# 2_Main_V2_4.net
KiCad netlist of a schematic drawn in Altium Designer
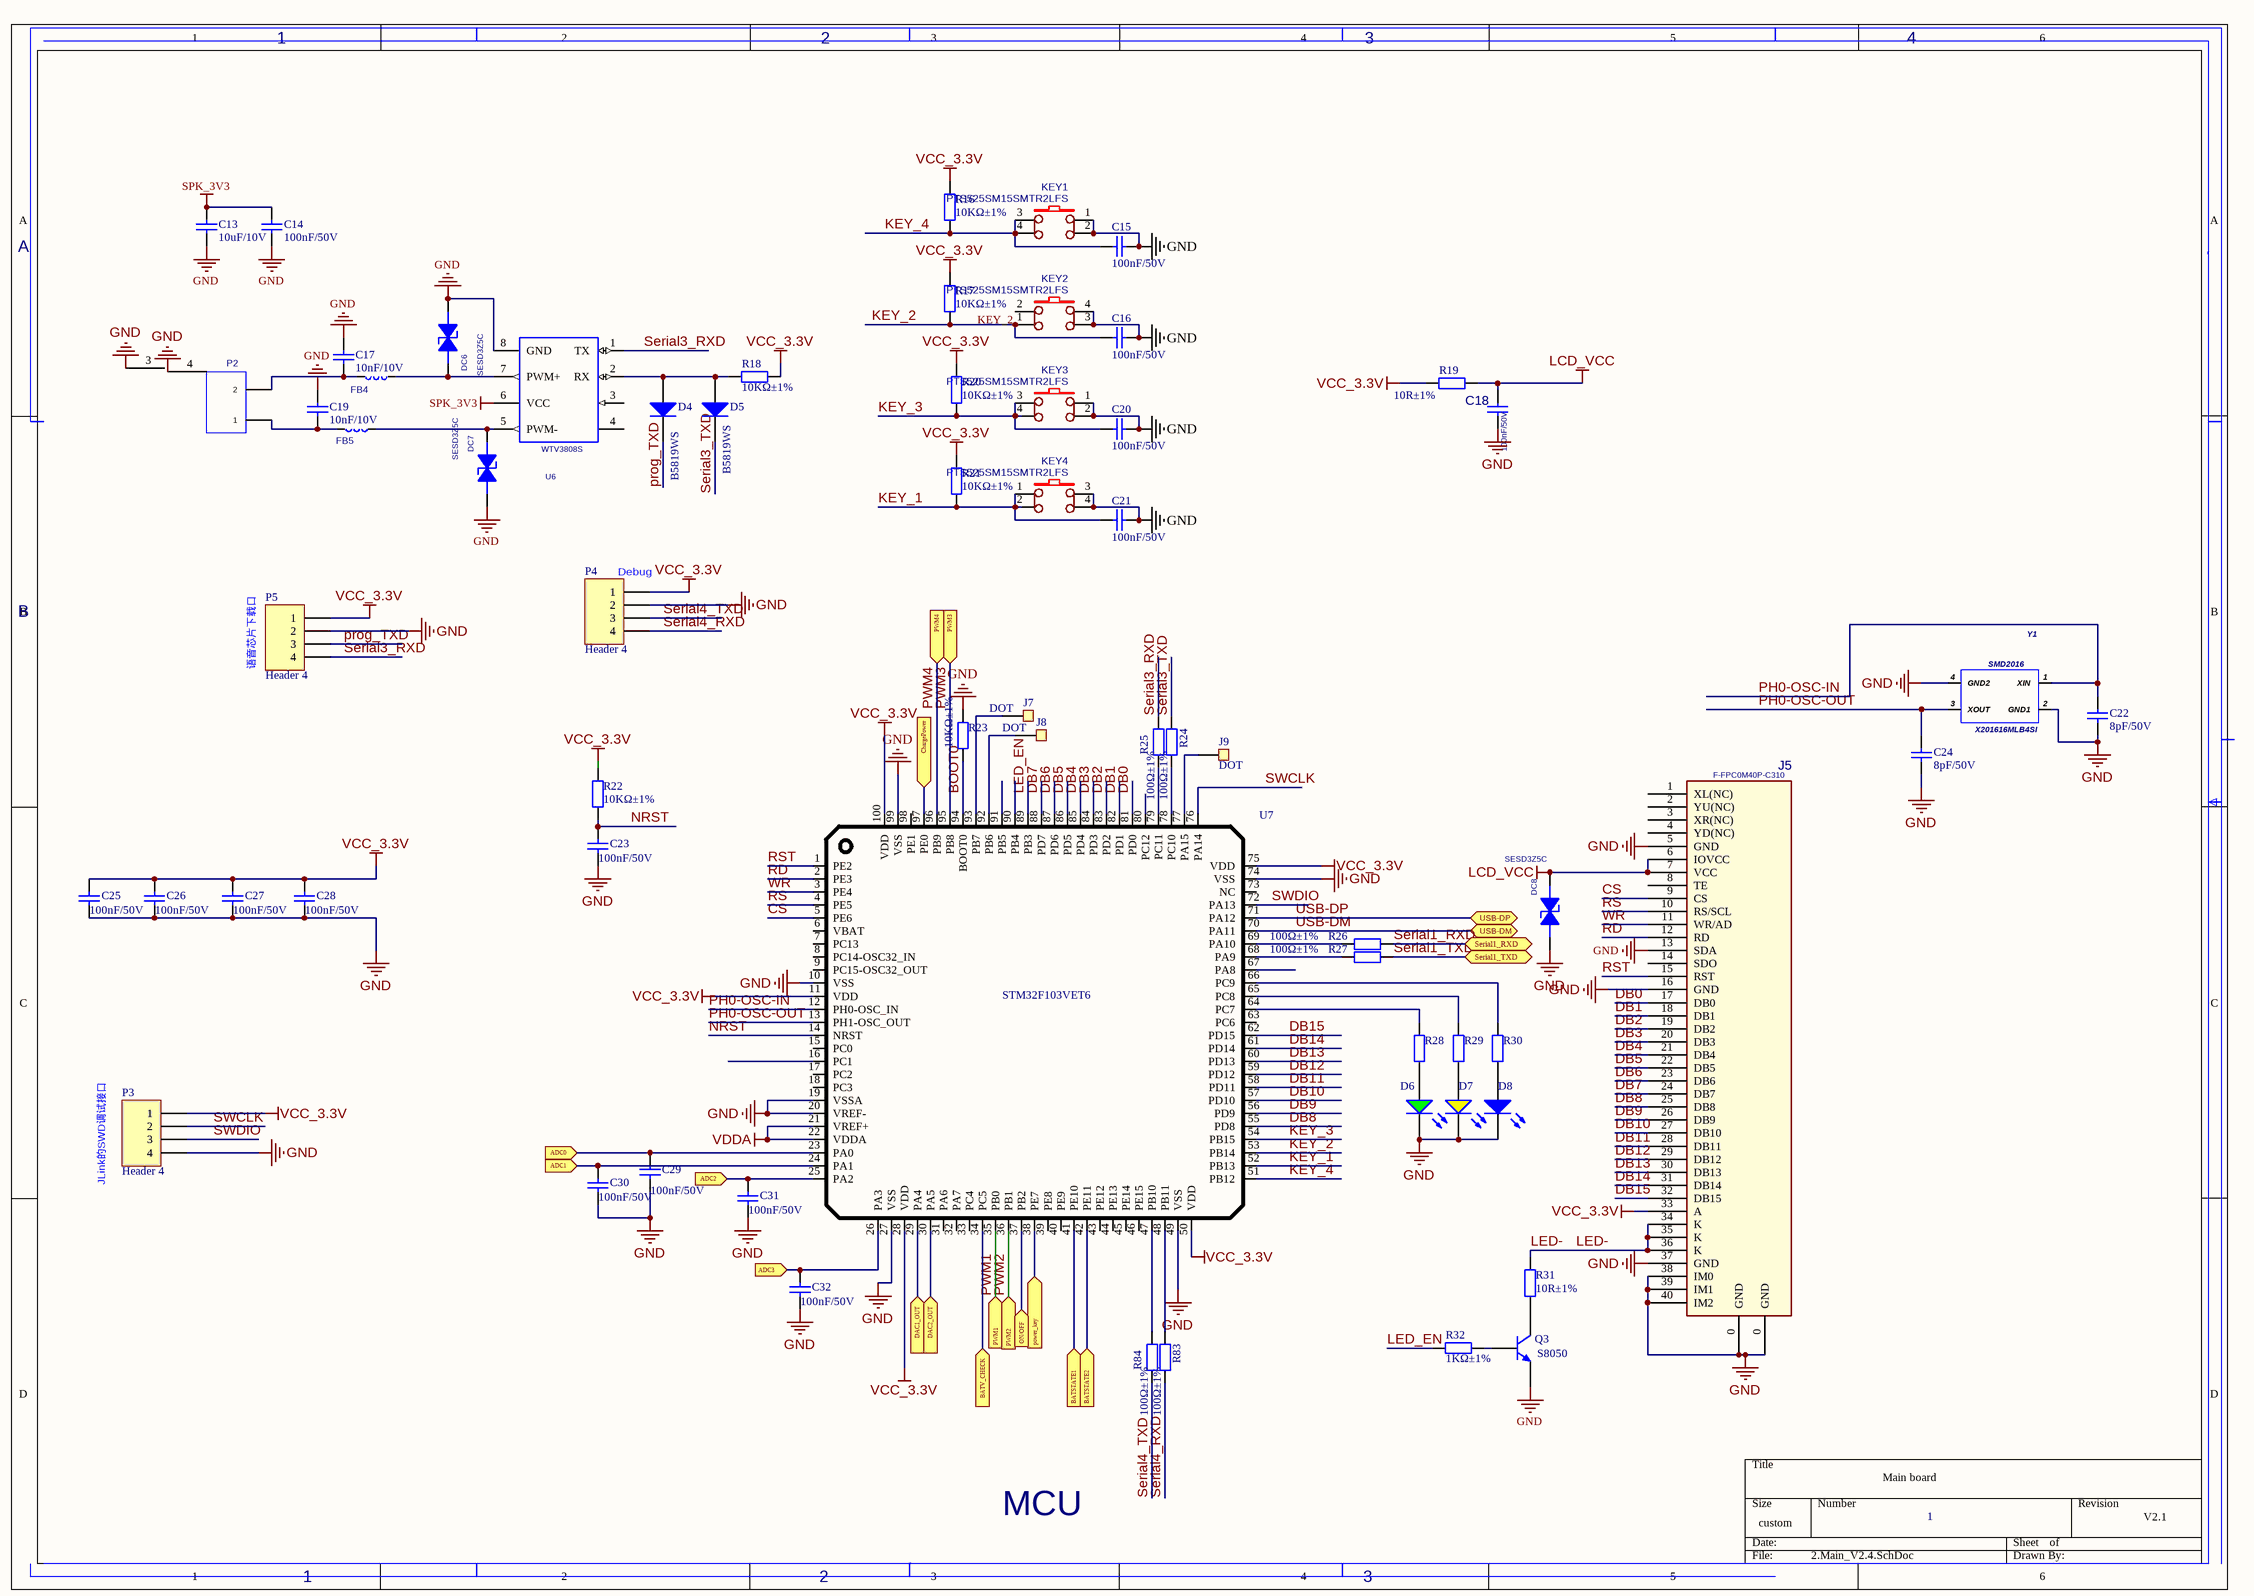
[diagram p0: 2.Main_V2.4.SchDoc]

(export (version "E")
  (design (tool "Eeschema 10.0.6"))
  (components
    (comp (ref "C13")
      (value "10uF/10V")
      (footprint "0603C")
      (description "Capacitor")
      (fields (field (name "PUBLISHER") "Altium Limited"))
      (libsource (lib "Miscellaneous Devices") (part "Cap"))
    )
    (comp (ref "C14")
      (value "100nF/50V")
      (footprint "0603C")
      (description "Capacitor 100nF/50V")
      (fields (field (name "PUBLISHER") "Altium Limited"))
      (libsource (lib "Miscellaneous Devices") (part "Cap"))
    )
    (comp (ref "C15")
      (value "100nF/50V")
      (footprint "0603C")
      (description "贴片电容100nF 10% 50V")
      (libsource (lib "Miscellaneous Devices LC") (part "0402 100nF (104) 10% 16V"))
    )
    (comp (ref "C16")
      (value "100nF/50V")
      (footprint "0603C")
      (description "贴片电容100nF 10% 50V")
      (libsource (lib "Miscellaneous Devices LC") (part "0402 100nF (104) 10% 16V"))
    )
    (comp (ref "C17")
      (value "10nF/10V")
      (footprint "0603C")
      (description "贴片电容")
      (libsource (lib "Miscellaneous Devices LC") (part "0402 10nF (103) 10% 50V"))
    )
    (comp (ref "C18") (value "100nF/50V") (footprint "0603C") (libsource (lib "*") (part "CAP103")))
    (comp (ref "C19")
      (value "10nF/10V")
      (footprint "0603C")
      (description "贴片电容")
      (libsource (lib "Miscellaneous Devices LC") (part "0402 10nF (103) 10% 50V"))
    )
    (comp (ref "C20")
      (value "100nF/50V")
      (footprint "0603C")
      (description "贴片电容100nF 10% 50V")
      (libsource (lib "Miscellaneous Devices LC") (part "0402 100nF (104) 10% 16V"))
    )
    (comp (ref "C21")
      (value "100nF/50V")
      (footprint "0603C")
      (description "贴片电容100nF 10% 50V")
      (libsource (lib "Miscellaneous Devices LC") (part "0402 100nF (104) 10% 16V"))
    )
    (comp (ref "C22")
      (value "8pF/50V")
      (footprint "0603C")
      (description "贴片电容")
      (libsource (lib "Miscellaneous Devices LC") (part "0402 6.8pF (6R8) 0.25pF 50V"))
    )
    (comp (ref "C23")
      (value "100nF/50V")
      (footprint "0603C")
      (description "贴片电容100nF 10% 50V")
      (libsource (lib "Miscellaneous Devices LC") (part "0402 100nF (104) 10% 16V"))
    )
    (comp (ref "C24")
      (value "8pF/50V")
      (footprint "0603C")
      (description "贴片电容")
      (libsource (lib "Miscellaneous Devices LC") (part "0402 6.8pF (6R8) 0.25pF 50V"))
    )
    (comp (ref "C25")
      (value "100nF/50V")
      (footprint "0603C")
      (description "贴片电容100nF 10% 50V")
      (libsource (lib "Miscellaneous Devices LC") (part "0402 100nF (104) 10% 16V"))
    )
    (comp (ref "C26")
      (value "100nF/50V")
      (footprint "0603C")
      (description "贴片电容100nF 10% 50V")
      (libsource (lib "Miscellaneous Devices LC") (part "0402 100nF (104) 10% 16V"))
    )
    (comp (ref "C27")
      (value "100nF/50V")
      (footprint "0603C")
      (description "贴片电容100nF 10% 50V")
      (libsource (lib "Miscellaneous Devices LC") (part "0402 100nF (104) 10% 16V"))
    )
    (comp (ref "C28")
      (value "100nF/50V")
      (footprint "0603C")
      (description "贴片电容100nF 10% 50V")
      (libsource (lib "Miscellaneous Devices LC") (part "0402 100nF (104) 10% 16V"))
    )
    (comp (ref "C29")
      (value "100nF/50V")
      (footprint "0603C")
      (description "贴片电容100nF 10% 50V")
      (libsource (lib "Miscellaneous Devices LC") (part "0402 100nF (104) 10% 16V"))
    )
    (comp (ref "C30")
      (value "100nF/50V")
      (footprint "0603C")
      (description "贴片电容100nF 10% 50V")
      (libsource (lib "Miscellaneous Devices LC") (part "0402 100nF (104) 10% 16V"))
    )
    (comp (ref "C31")
      (value "100nF/50V")
      (footprint "0603C")
      (description "贴片电容100nF 10% 50V")
      (libsource (lib "Miscellaneous Devices LC") (part "0402 100nF (104) 10% 16V"))
    )
    (comp (ref "C32")
      (value "100nF/50V")
      (footprint "0603C")
      (description "贴片电容100nF 10% 50V")
      (libsource (lib "Miscellaneous Devices LC") (part "0402 100nF (104) 10% 16V"))
    )
    (comp (ref "D4")
      (value "B5819WS")
      (footprint "SOD-323")
      (description "CJ(江苏长电/长晶)")
      (fields (field (name "PUBLISHER") "Altium Limited"))
      (libsource (lib "Miscellaneous Devices") (part "Diode"))
    )
    (comp (ref "D5")
      (value "B5819WS")
      (footprint "SOD-323")
      (description "CJ(江苏长电/长晶)")
      (fields (field (name "PUBLISHER") "Altium Limited"))
      (libsource (lib "Miscellaneous Devices") (part "Diode"))
    )
    (comp (ref "D6")
      (value "19-217/GHC-YR1S2/3T")
      (footprint "0603_LED_S1")
      (description "发光二极管 EVERLIGHT(亿光) 0603 翠绿")
      (libsource (lib "Miscellaneous Devices LC") (part "0603 绿灯"))
    )
    (comp (ref "D7")
      (value "19-213/Y2C-CQ2R2L/3T(CY)")
      (footprint "0603_LED_S1")
      (description "发光二极管  0603 黄灯")
      (libsource (lib "Miscellaneous Devices LC") (part "0603 黄灯"))
    )
    (comp (ref "D8")
      (value "19-217/GHC-YR1S2/3T")
      (footprint "0603_LED_S1")
      (description "发光二极管 EVERLIGHT(亿光) 0603 蓝灯")
      (libsource (lib "Miscellaneous Devices LC") (part "0603 蓝灯"))
    )
    (comp (ref "DC6") (value "SESD3Z5C") (footprint "SOD323") (libsource (lib "*") (part "ESD5451X_Dup1")))
    (comp (ref "DC7") (value "SESD3Z5C") (footprint "SOD323") (libsource (lib "*") (part "ESD5451X_Dup1")))
    (comp (ref "DC8") (value "SESD3Z5C") (footprint "SOD323") (libsource (lib "*") (part "ESD5451X_Dup1")))
    (comp (ref "FB4")
      (value "BLM18AG601SN1D")
      (footprint "R0603")
      (description "磁珠/600Ω@100MHz ±25% BLM18AG601SN1D 0603")
      (libsource (lib "*") (part "ZXC"))
    )
    (comp (ref "FB5")
      (value "BLM18AG601SN1D")
      (footprint "R0603")
      (description "磁珠/600Ω@100MHz ±25% BLM18AG601SN1D 0603")
      (libsource (lib "*") (part "ZXC"))
    )
    (comp (ref "J5")
      (value "F-FPC0M40P-C310")
      (footprint "FPC0.5 2H-WS-40P")
      (libsource (lib "phil_sch_lirb") (part "FPC_40_LVDS"))
    )
    (comp (ref "J7") (value "DOT") (footprint "TP100MH") (libsource (lib "MySchLib") (part "DOT")))
    (comp (ref "J8") (value "DOT") (footprint "TP100MH") (libsource (lib "MySchLib") (part "DOT")))
    (comp (ref "J9") (value "DOT") (footprint "TP100MH") (libsource (lib "MySchLib") (part "DOT")))
    (comp (ref "KEY1")
      (value "PTS525SM15SMTR2LFS")
      (footprint "KEY_KSC221JLFS")
      (fields
        (field (name "BOM_SUPPLIER PART") "C59980")
        (field (name "BOM_MANUFACTURER PART") "button6*6*8.5")
      )
      (libsource (lib "altium-import") (part "root_0_button6*6*8.5_"))
    )
    (comp (ref "KEY2")
      (value "PTS525SM15SMTR2LFS")
      (footprint "KEY_KSC221JLFS")
      (fields
        (field (name "BOM_SUPPLIER PART") "C59980")
        (field (name "BOM_MANUFACTURER PART") "button6*6*8.5")
      )
      (libsource (lib "") (part "root_0_button6*6*8.5__2"))
    )
    (comp (ref "KEY3")
      (value "PTS525SM15SMTR2LFS")
      (footprint "KEY_KSC221JLFS")
      (fields
        (field (name "BOM_SUPPLIER PART") "C59980")
        (field (name "BOM_MANUFACTURER PART") "button6*6*8.5")
      )
      (libsource (lib "altium-import") (part "root_0_button6*6*8.5_"))
    )
    (comp (ref "KEY4")
      (value "PTS525SM15SMTR2LFS")
      (footprint "KEY_KSC221JLFS")
      (fields
        (field (name "BOM_SUPPLIER PART") "C59980")
        (field (name "BOM_MANUFACTURER PART") "button6*6*8.5")
      )
      (libsource (lib "") (part "root_0_button6*6*8.5__1"))
    )
    (comp (ref "P2")
      (value "HX 1.25-2P WT")
      (footprint "1.25-2P")
      (description "SHOU HAN(首韩) 间距：1.25mm 插针结构：1x2P 排数：1 每排PIN数：2 间距：1.25mm")
      (fields (field (name "PUBLISHER") "Altium Limited"))
      (libsource (lib "*") (part "DIP-2.0-2P"))
    )
    (comp (ref "P3")
      (value "Header 4")
      (footprint "HDR1X4")
      (description "Header, 4-Pin")
      (fields (field (name "PUBLISHER") "Altium Limited"))
      (libsource (lib "Miscellaneous Connectors") (part "Header 4"))
    )
    (comp (ref "P4")
      (value "Header 4")
      (footprint "HDR1X4")
      (description "Header, 4-Pin")
      (fields (field (name "PUBLISHER") "Altium Limited"))
      (libsource (lib "Miscellaneous Connectors") (part "Header 4"))
    )
    (comp (ref "P5")
      (value "Header 4")
      (footprint "HDR1X4")
      (description "Header, 4-Pin")
      (fields (field (name "PUBLISHER") "Altium Limited"))
      (libsource (lib "Miscellaneous Connectors") (part "Header 4"))
    )
    (comp (ref "Q3")
      (value "S8050")
      (footprint "SOT-23")
      (description "三极管")
      (libsource (lib "Miscellaneous Devices LC") (part "SOT-23 SS8050 Y1"))
    )
    (comp (ref "R16")
      (value "10KΩ±1%")
      (footprint "0603R")
      (description "贴片电阻")
      (libsource (lib "Miscellaneous Devices LC") (part "0402 10KΩ (1002) 1%"))
    )
    (comp (ref "R17")
      (value "10KΩ±1%")
      (footprint "0603R")
      (description "贴片电阻")
      (libsource (lib "Miscellaneous Devices LC") (part "0402 10KΩ (1002) 1%"))
    )
    (comp (ref "R18")
      (value "10KΩ±1%")
      (footprint "0603R")
      (description "贴片电阻")
      (libsource (lib "") (part "0402 10KΩ (1002) 1%_2"))
    )
    (comp (ref "R19")
      (value "10R±1%")
      (footprint "0603R")
      (description "贴片电阻")
      (libsource (lib "Miscellaneous Devices LC") (part "0603 10Ω (10R0) 1%"))
    )
    (comp (ref "R20")
      (value "10KΩ±1%")
      (footprint "0603R")
      (description "贴片电阻")
      (libsource (lib "Miscellaneous Devices LC") (part "0402 10KΩ (1002) 1%"))
    )
    (comp (ref "R21")
      (value "10KΩ±1%")
      (footprint "0603R")
      (description "贴片电阻")
      (libsource (lib "Miscellaneous Devices LC") (part "0402 10KΩ (1002) 1%"))
    )
    (comp (ref "R22")
      (value "10KΩ±1%")
      (footprint "0603R")
      (description "贴片电阻")
      (libsource (lib "Miscellaneous Devices LC") (part "0402 10KΩ (1002) 1%"))
    )
    (comp (ref "R23")
      (value "10KΩ±1%")
      (footprint "0603R")
      (description "贴片电阻")
      (libsource (lib "") (part "0402 10KΩ (1002) 1%_1"))
    )
    (comp (ref "R24")
      (value "100Ω±1%")
      (footprint "0603R")
      (description "贴片电阻")
      (libsource (lib "") (part "0603 100Ω (1000) 1%_1"))
    )
    (comp (ref "R25")
      (value "100Ω±1%")
      (footprint "0603R")
      (description "贴片电阻")
      (libsource (lib "") (part "0603 100Ω (1000) 1%_1"))
    )
    (comp (ref "R26")
      (value "100Ω±1%")
      (footprint "0603R")
      (description "贴片电阻")
      (libsource (lib "Miscellaneous Devices LC") (part "0603 100Ω (1000) 1%"))
    )
    (comp (ref "R27")
      (value "100Ω±1%")
      (footprint "0603R")
      (description "贴片电阻")
      (libsource (lib "Miscellaneous Devices LC") (part "0603 100Ω (1000) 1%"))
    )
    (comp (ref "R28")
      (value "1.5KΩ±1%")
      (footprint "0603R")
      (description "贴片电阻")
      (libsource (lib "Miscellaneous Devices LC") (part "0603 1.5KΩ (1501) 1%"))
    )
    (comp (ref "R29")
      (value "1.5KΩ±1%")
      (footprint "0603R")
      (description "贴片电阻")
      (libsource (lib "Miscellaneous Devices LC") (part "0603 1.5KΩ (1501) 1%"))
    )
    (comp (ref "R30")
      (value "1.5KΩ±1%")
      (footprint "0603R")
      (description "贴片电阻")
      (libsource (lib "Miscellaneous Devices LC") (part "0603 1.5KΩ (1501) 1%"))
    )
    (comp (ref "R31")
      (value "10R±1%")
      (footprint "0805_R")
      (description "贴片电阻")
      (libsource (lib "") (part "0603 10Ω (10R0) 1%_1"))
    )
    (comp (ref "R32")
      (value "1KΩ±1%")
      (footprint "0603R")
      (description "贴片电阻")
      (libsource (lib "Miscellaneous Devices LC") (part "0603 1KΩ (1001) 1%"))
    )
    (comp (ref "R83")
      (value "100Ω±1%")
      (footprint "0603R")
      (description "贴片电阻")
      (libsource (lib "") (part "0603 100Ω (1000) 1%_1"))
    )
    (comp (ref "R84")
      (value "100Ω±1%")
      (footprint "0603R")
      (description "贴片电阻")
      (libsource (lib "") (part "0603 100Ω (1000) 1%_1"))
    )
    (comp (ref "U6")
      (value "WTV3808S")
      (footprint "SOP-8_150mil")
      (description "WTV3808S  380")
      (fields
        (field (name "MANUFACTURER_PART_NUMBER") "OPA335AIDBVR")
        (field (name "COPYRIGHT") "Copyright (C) 2022 Ultra Librarian. All rights reserved.")
      )
      (libsource (lib "FES_VNS_V1.0x2") (part "WTVXXX8S"))
    )
    (comp (ref "U7")
      (value "STM32F103VET6")
      (footprint "LQFP-100_14x14x05P")
      (description "STM32F407VETx")
      (libsource (lib "FES_VNS_V1.0x2") (part "STM32F407VETx"))
    )
    (comp (ref "Y1")
      (value "X201616MLB4SI")
      (footprint "SMD_2016")
      (description "YXC(扬兴晶振) X201616MLB4SI  16MHz 频率公差：±10ppm")
      (fields
        (field (name "MANUFACTURER") "Hosonic(鸿星电子)")
        (field (name "PCB DECAL") "SMD2016")
        (field (name "CREATED_BY") "JJJ")
      )
      (libsource (lib "*") (part "CRYSTAL_4P"))
    )
  )
  (nets
    (net (code "1") (name "/ADC0") (class "Default")
      (node (ref "C29") (pin "2") (pinfunction "2_2") (pintype "passive"))
      (node (ref "U7") (pin "23") (pinfunction "PA0_23") (pintype "passive"))
    )
    (net (code "2") (name "/ADC1") (class "Default")
      (node (ref "C30") (pin "2") (pinfunction "2_2") (pintype "passive"))
      (node (ref "U7") (pin "24") (pinfunction "PA1_24") (pintype "passive"))
    )
    (net (code "3") (name "/ADC2") (class "Default")
      (node (ref "C31") (pin "2") (pinfunction "2_2") (pintype "passive"))
      (node (ref "U7") (pin "25") (pinfunction "PA2_25") (pintype "passive"))
    )
    (net (code "4") (name "/ADC3") (class "Default")
      (node (ref "C32") (pin "2") (pinfunction "2_2") (pintype "passive"))
      (node (ref "U7") (pin "26") (pinfunction "PA3_26") (pintype "passive"))
    )
    (net (code "5") (name "/BATSTATE1") (class "Default")
      (node (ref "U7") (pin "41") (pinfunction "PE10_41") (pintype "passive"))
    )
    (net (code "6") (name "/BATSTATE2") (class "Default")
      (node (ref "U7") (pin "42") (pinfunction "PE11_42") (pintype "passive"))
    )
    (net (code "7") (name "/BATV_CHECK") (class "Default")
      (node (ref "U7") (pin "34") (pinfunction "PC5_34") (pintype "passive"))
    )
    (net (code "8") (name "/BOOT0") (class "Default")
      (node (ref "R23") (pin "2") (pinfunction "2_2") (pintype "passive"))
      (node (ref "U7") (pin "94") (pinfunction "BOOT0_94") (pintype "passive"))
    )
    (net (code "9") (name "/CS") (class "Default")
      (node (ref "J5") (pin "9") (pinfunction "CS_9") (pintype "passive"))
      (node (ref "U7") (pin "5") (pinfunction "PE6_5") (pintype "passive"))
    )
    (net (code "10") (name "/ChargePower") (class "Default")
      (node (ref "U7") (pin "97") (pinfunction "PE0_97") (pintype "passive"))
    )
    (net (code "11") (name "/DAC1_OUT") (class "Default")
      (node (ref "U7") (pin "29") (pinfunction "PA4_29") (pintype "passive"))
    )
    (net (code "12") (name "/DAC2_OUT") (class "Default")
      (node (ref "U7") (pin "30") (pinfunction "PA5_30") (pintype "passive"))
    )
    (net (code "13") (name "/DB0") (class "Default")
      (node (ref "J5") (pin "17") (pinfunction "DB0_17") (pintype "passive"))
      (node (ref "U7") (pin "81") (pinfunction "PD0_81") (pintype "passive"))
    )
    (net (code "14") (name "/DB1") (class "Default")
      (node (ref "J5") (pin "18") (pinfunction "DB1_18") (pintype "passive"))
      (node (ref "U7") (pin "82") (pinfunction "PD1_82") (pintype "passive"))
    )
    (net (code "15") (name "/DB2") (class "Default")
      (node (ref "J5") (pin "19") (pinfunction "DB2_19") (pintype "passive"))
      (node (ref "U7") (pin "83") (pinfunction "PD2_83") (pintype "passive"))
    )
    (net (code "16") (name "/DB3") (class "Default")
      (node (ref "J5") (pin "20") (pinfunction "DB3_20") (pintype "passive"))
      (node (ref "U7") (pin "84") (pinfunction "PD3_84") (pintype "passive"))
    )
    (net (code "17") (name "/DB4") (class "Default")
      (node (ref "J5") (pin "21") (pinfunction "DB4_21") (pintype "passive"))
      (node (ref "U7") (pin "85") (pinfunction "PD4_85") (pintype "passive"))
    )
    (net (code "18") (name "/DB5") (class "Default")
      (node (ref "J5") (pin "22") (pinfunction "DB5_22") (pintype "passive"))
      (node (ref "U7") (pin "86") (pinfunction "PD5_86") (pintype "passive"))
    )
    (net (code "19") (name "/DB6") (class "Default")
      (node (ref "J5") (pin "23") (pinfunction "DB6_23") (pintype "passive"))
      (node (ref "U7") (pin "87") (pinfunction "PD6_87") (pintype "passive"))
    )
    (net (code "20") (name "/DB7") (class "Default")
      (node (ref "J5") (pin "24") (pinfunction "DB7_24") (pintype "passive"))
      (node (ref "U7") (pin "88") (pinfunction "PD7_88") (pintype "passive"))
    )
    (net (code "21") (name "/DB8") (class "Default")
      (node (ref "J5") (pin "25") (pinfunction "DB8_25") (pintype "passive"))
      (node (ref "U7") (pin "55") (pinfunction "PD8_55") (pintype "passive"))
    )
    (net (code "22") (name "/DB9") (class "Default")
      (node (ref "J5") (pin "26") (pinfunction "DB9_26") (pintype "passive"))
      (node (ref "U7") (pin "56") (pinfunction "PD9_56") (pintype "passive"))
    )
    (net (code "23") (name "/DB10") (class "Default")
      (node (ref "J5") (pin "27") (pinfunction "DB10_27") (pintype "passive"))
      (node (ref "U7") (pin "57") (pinfunction "PD10_57") (pintype "passive"))
    )
    (net (code "24") (name "/DB11") (class "Default")
      (node (ref "J5") (pin "28") (pinfunction "DB11_28") (pintype "passive"))
      (node (ref "U7") (pin "58") (pinfunction "PD11_58") (pintype "passive"))
    )
    (net (code "25") (name "/DB12") (class "Default")
      (node (ref "J5") (pin "29") (pinfunction "DB12_29") (pintype "passive"))
      (node (ref "U7") (pin "59") (pinfunction "PD12_59") (pintype "passive"))
    )
    (net (code "26") (name "/DB13") (class "Default")
      (node (ref "J5") (pin "30") (pinfunction "DB13_30") (pintype "passive"))
      (node (ref "U7") (pin "60") (pinfunction "PD13_60") (pintype "passive"))
    )
    (net (code "27") (name "/DB14") (class "Default")
      (node (ref "J5") (pin "31") (pinfunction "DB14_31") (pintype "passive"))
      (node (ref "U7") (pin "61") (pinfunction "PD14_61") (pintype "passive"))
    )
    (net (code "28") (name "/DB15") (class "Default")
      (node (ref "J5") (pin "32") (pinfunction "DB15_32") (pintype "passive"))
      (node (ref "U7") (pin "62") (pinfunction "PD15_62") (pintype "passive"))
    )
    (net (code "29") (name "/KEY_1") (class "Default")
      (node (ref "C21") (pin "2") (pinfunction "2_2") (pintype "passive"))
      (node (ref "KEY4") (pin "1") (pinfunction "1_1") (pintype "passive"))
      (node (ref "KEY4") (pin "2") (pinfunction "2_2") (pintype "passive"))
      (node (ref "R21") (pin "1") (pinfunction "1_1") (pintype "passive"))
      (node (ref "U7") (pin "52") (pinfunction "PB13_52") (pintype "passive"))
    )
    (net (code "30") (name "/KEY_2") (class "Default")
      (node (ref "C16") (pin "2") (pinfunction "2_2") (pintype "passive"))
      (node (ref "KEY2") (pin "1") (pinfunction "1_1") (pintype "passive"))
      (node (ref "KEY2") (pin "2") (pinfunction "2_2") (pintype "passive"))
      (node (ref "R17") (pin "1") (pinfunction "1_1") (pintype "passive"))
      (node (ref "U7") (pin "53") (pinfunction "PB14_53") (pintype "passive"))
    )
    (net (code "31") (name "/KEY_3") (class "Default")
      (node (ref "C20") (pin "2") (pinfunction "2_2") (pintype "passive"))
      (node (ref "KEY3") (pin "3") (pinfunction "3_3") (pintype "passive"))
      (node (ref "KEY3") (pin "4") (pinfunction "4_4") (pintype "passive"))
      (node (ref "R20") (pin "1") (pinfunction "1_1") (pintype "passive"))
      (node (ref "U7") (pin "54") (pinfunction "PB15_54") (pintype "passive"))
    )
    (net (code "32") (name "/KEY_4") (class "Default")
      (node (ref "C15") (pin "2") (pinfunction "2_2") (pintype "passive"))
      (node (ref "KEY1") (pin "3") (pinfunction "3_3") (pintype "passive"))
      (node (ref "KEY1") (pin "4") (pinfunction "4_4") (pintype "passive"))
      (node (ref "R16") (pin "1") (pinfunction "1_1") (pintype "passive"))
      (node (ref "U7") (pin "51") (pinfunction "PB12_51") (pintype "passive"))
    )
    (net (code "33") (name "/LED-") (class "Default")
      (node (ref "J5") (pin "34") (pinfunction "K_34") (pintype "passive"))
      (node (ref "J5") (pin "35") (pinfunction "K_35") (pintype "passive"))
      (node (ref "J5") (pin "36") (pinfunction "K_36") (pintype "passive"))
      (node (ref "R31") (pin "2") (pinfunction "2_2") (pintype "passive"))
    )
    (net (code "34") (name "/LED_EN") (class "Default")
      (node (ref "R32") (pin "2") (pinfunction "2_2") (pintype "passive"))
      (node (ref "U7") (pin "89") (pinfunction "PB3_89") (pintype "passive"))
    )
    (net (code "35") (name "/NRST") (class "Default")
      (node (ref "C23") (pin "2") (pinfunction "2_2") (pintype "passive"))
      (node (ref "R22") (pin "1") (pinfunction "1_1") (pintype "passive"))
      (node (ref "U7") (pin "14") (pinfunction "NRST_14") (pintype "passive"))
    )
    (net (code "36") (name "/ON{slash}OFF") (class "Default")
      (node (ref "U7") (pin "37") (pinfunction "PB2_37") (pintype "passive"))
    )
    (net (code "37") (name "/PH0-OSC-IN") (class "Default")
      (node (ref "C22") (pin "2") (pinfunction "2_2") (pintype "passive"))
      (node (ref "U7") (pin "12") (pinfunction "PH0-OSC_IN_12") (pintype "passive"))
      (node (ref "Y1") (pin "1") (pinfunction "XIN_1") (pintype "passive"))
    )
    (net (code "38") (name "/PH0-OSC-OUT") (class "Default")
      (node (ref "C24") (pin "2") (pinfunction "2_2") (pintype "passive"))
      (node (ref "U7") (pin "13") (pinfunction "PH1-OSC_OUT_13") (pintype "passive"))
      (node (ref "Y1") (pin "3") (pinfunction "XOUT_3") (pintype "passive"))
    )
    (net (code "39") (name "/PWM1") (class "Default")
      (node (ref "U7") (pin "35") (pinfunction "PB0_35") (pintype "passive"))
    )
    (net (code "40") (name "/PWM2") (class "Default")
      (node (ref "U7") (pin "36") (pinfunction "PB1_36") (pintype "passive"))
    )
    (net (code "41") (name "/PWM3") (class "Default")
      (node (ref "U7") (pin "95") (pinfunction "PB8_95") (pintype "passive"))
    )
    (net (code "42") (name "/PWM4") (class "Default")
      (node (ref "U7") (pin "96") (pinfunction "PB9_96") (pintype "passive"))
    )
    (net (code "43") (name "/RD") (class "Default")
      (node (ref "J5") (pin "12") (pinfunction "RD_12") (pintype "passive"))
      (node (ref "U7") (pin "2") (pinfunction "PE3_2") (pintype "passive"))
    )
    (net (code "44") (name "/RS") (class "Default")
      (node (ref "J5") (pin "10") (pinfunction "RS/SCL_10") (pintype "passive"))
      (node (ref "U7") (pin "4") (pinfunction "PE5_4") (pintype "passive"))
    )
    (net (code "45") (name "/RST") (class "Default")
      (node (ref "J5") (pin "15") (pinfunction "RST_15") (pintype "passive"))
      (node (ref "U7") (pin "1") (pinfunction "PE2_1") (pintype "passive"))
    )
    (net (code "46") (name "/SWCLK") (class "Default")
      (node (ref "P3") (pin "2") (pinfunction "2_2") (pintype "passive"))
      (node (ref "U7") (pin "76") (pinfunction "PA14_76") (pintype "passive"))
    )
    (net (code "47") (name "/SWDIO") (class "Default")
      (node (ref "P3") (pin "3") (pinfunction "3_3") (pintype "passive"))
      (node (ref "U7") (pin "72") (pinfunction "PA13_72") (pintype "passive"))
    )
    (net (code "48") (name "/Serial1_RXD") (class "Default")
      (node (ref "R26") (pin "1") (pinfunction "1_1") (pintype "passive"))
    )
    (net (code "49") (name "/Serial1_TXD") (class "Default")
      (node (ref "R27") (pin "1") (pinfunction "1_1") (pintype "passive"))
    )
    (net (code "50") (name "/Serial3_RXD") (class "Default")
      (node (ref "P5") (pin "4") (pinfunction "4_4") (pintype "passive"))
      (node (ref "R25") (pin "1") (pinfunction "1_1") (pintype "passive"))
      (node (ref "U6") (pin "1") (pinfunction "TX_1") (pintype "bidirectional"))
    )
    (net (code "51") (name "/Serial3_TXD") (class "Default")
      (node (ref "D5") (pin "2") (pinfunction "K_2") (pintype "passive"))
      (node (ref "R24") (pin "1") (pinfunction "1_1") (pintype "passive"))
    )
    (net (code "52") (name "/Serial4_RXD") (class "Default")
      (node (ref "P4") (pin "4") (pinfunction "4_4") (pintype "passive"))
      (node (ref "R83") (pin "2") (pinfunction "2_2") (pintype "passive"))
    )
    (net (code "53") (name "/Serial4_TXD") (class "Default")
      (node (ref "P4") (pin "3") (pinfunction "3_3") (pintype "passive"))
      (node (ref "R84") (pin "2") (pinfunction "2_2") (pintype "passive"))
    )
    (net (code "54") (name "/USB-DM") (class "Default")
      (node (ref "U7") (pin "70") (pinfunction "PA11_70") (pintype "passive"))
    )
    (net (code "55") (name "/USB-DP") (class "Default")
      (node (ref "U7") (pin "71") (pinfunction "PA12_71") (pintype "passive"))
    )
    (net (code "56") (name "/WR") (class "Default")
      (node (ref "J5") (pin "11") (pinfunction "WR/AD_11") (pintype "passive"))
      (node (ref "U7") (pin "3") (pinfunction "PE4_3") (pintype "passive"))
    )
    (net (code "57") (name "/power_key") (class "Default")
      (node (ref "U7") (pin "38") (pinfunction "PE7_38") (pintype "passive"))
    )
    (net (code "58") (name "/prog_TXD") (class "Default")
      (node (ref "D4") (pin "2") (pinfunction "K_2") (pintype "passive"))
      (node (ref "P5") (pin "3") (pinfunction "3_3") (pintype "passive"))
    )
    (net (code "59") (name "GND") (class "Default")
      (node (ref "C13") (pin "2") (pinfunction "2_2") (pintype "passive"))
      (node (ref "C14") (pin "1") (pinfunction "1_1") (pintype "passive"))
      (node (ref "C15") (pin "1") (pinfunction "1_1") (pintype "passive"))
      (node (ref "C16") (pin "1") (pinfunction "1_1") (pintype "passive"))
      (node (ref "C17") (pin "1") (pinfunction "1_1") (pintype "passive"))
      (node (ref "C18") (pin "2") (pinfunction "2_2") (pintype "passive"))
      (node (ref "C19") (pin "1") (pinfunction "1_1") (pintype "passive"))
      (node (ref "C20") (pin "1") (pinfunction "1_1") (pintype "passive"))
      (node (ref "C21") (pin "1") (pinfunction "1_1") (pintype "passive"))
      (node (ref "C22") (pin "1") (pinfunction "1_1") (pintype "passive"))
      (node (ref "C23") (pin "1") (pinfunction "1_1") (pintype "passive"))
      (node (ref "C24") (pin "1") (pinfunction "1_1") (pintype "passive"))
      (node (ref "C25") (pin "1") (pinfunction "1_1") (pintype "passive"))
      (node (ref "C26") (pin "1") (pinfunction "1_1") (pintype "passive"))
      (node (ref "C27") (pin "1") (pinfunction "1_1") (pintype "passive"))
      (node (ref "C28") (pin "1") (pinfunction "1_1") (pintype "passive"))
      (node (ref "C29") (pin "1") (pinfunction "1_1") (pintype "passive"))
      (node (ref "C30") (pin "1") (pinfunction "1_1") (pintype "passive"))
      (node (ref "C31") (pin "1") (pinfunction "1_1") (pintype "passive"))
      (node (ref "C32") (pin "1") (pinfunction "1_1") (pintype "passive"))
      (node (ref "D6") (pin "K") (pinfunction "K_K") (pintype "passive"))
      (node (ref "D7") (pin "K") (pinfunction "K_K") (pintype "passive"))
      (node (ref "D8") (pin "K") (pinfunction "K_K") (pintype "passive"))
      (node (ref "DC6") (pin "1") (pinfunction "ANODE_1") (pintype "passive"))
      (node (ref "DC7") (pin "1") (pinfunction "ANODE_1") (pintype "passive"))
      (node (ref "DC8") (pin "1") (pinfunction "ANODE_1") (pintype "passive"))
      (node (ref "J5") (pin "0") (pinfunction "GND_0") (pintype "passive"))
      (node (ref "J5") (pin "13") (pinfunction "SDA_13") (pintype "passive"))
      (node (ref "J5") (pin "16") (pinfunction "GND_16") (pintype "passive"))
      (node (ref "J5") (pin "37") (pinfunction "GND_37") (pintype "passive"))
      (node (ref "J5") (pin "38") (pinfunction "IM0_38") (pintype "passive"))
      (node (ref "J5") (pin "39") (pinfunction "IM1_39") (pintype "passive"))
      (node (ref "J5") (pin "40") (pinfunction "IM2_40") (pintype "passive"))
      (node (ref "J5") (pin "5") (pinfunction "GND_5") (pintype "passive"))
      (node (ref "KEY1") (pin "1") (pinfunction "1_1") (pintype "passive"))
      (node (ref "KEY1") (pin "2") (pinfunction "2_2") (pintype "passive"))
      (node (ref "KEY2") (pin "3") (pinfunction "3_3") (pintype "passive"))
      (node (ref "KEY2") (pin "4") (pinfunction "4_4") (pintype "passive"))
      (node (ref "KEY3") (pin "1") (pinfunction "1_1") (pintype "passive"))
      (node (ref "KEY3") (pin "2") (pinfunction "2_2") (pintype "passive"))
      (node (ref "KEY4") (pin "3") (pinfunction "3_3") (pintype "passive"))
      (node (ref "KEY4") (pin "4") (pinfunction "4_4") (pintype "passive"))
      (node (ref "P2") (pin "3") (pinfunction "3_3") (pintype "passive"))
      (node (ref "P2") (pin "4") (pinfunction "4_4") (pintype "passive"))
      (node (ref "P3") (pin "4") (pinfunction "4_4") (pintype "passive"))
      (node (ref "P4") (pin "2") (pinfunction "2_2") (pintype "passive"))
      (node (ref "P5") (pin "2") (pinfunction "2_2") (pintype "passive"))
      (node (ref "Q3") (pin "2") (pinfunction "E_2") (pintype "passive"))
      (node (ref "R23") (pin "1") (pinfunction "1_1") (pintype "passive"))
      (node (ref "U6") (pin "8") (pinfunction "GND_8") (pintype "power_in"))
      (node (ref "U7") (pin "10") (pinfunction "VSS_10") (pintype "passive"))
      (node (ref "U7") (pin "19") (pinfunction "VSSA_19") (pintype "passive"))
      (node (ref "U7") (pin "20") (pinfunction "VREF-_20") (pintype "passive"))
      (node (ref "U7") (pin "27") (pinfunction "VSS_27") (pintype "passive"))
      (node (ref "U7") (pin "49") (pinfunction "VSS_49") (pintype "passive"))
      (node (ref "U7") (pin "74") (pinfunction "VSS_74") (pintype "passive"))
      (node (ref "U7") (pin "99") (pinfunction "VSS_99") (pintype "passive"))
      (node (ref "Y1") (pin "2") (pinfunction "GND1_2") (pintype "passive"))
      (node (ref "Y1") (pin "4") (pinfunction "GND2_4") (pintype "passive"))
    )
    (net (code "60") (name "LCD_VCC") (class "Default")
      (node (ref "C18") (pin "1") (pinfunction "1_1") (pintype "passive"))
      (node (ref "DC8") (pin "2") (pinfunction "CATHODE_2") (pintype "passive"))
      (node (ref "J5") (pin "6") (pinfunction "IOVCC_6") (pintype "passive"))
      (node (ref "J5") (pin "7") (pinfunction "VCC_7") (pintype "passive"))
      (node (ref "R19") (pin "1") (pinfunction "1_1") (pintype "passive"))
    )
    (net (code "61") (name "Net-(C17-Pad2)") (class "Default")
      (node (ref "C17") (pin "2") (pinfunction "2_2") (pintype "passive"))
      (node (ref "FB4") (pin "1") (pinfunction "1_1") (pintype "passive"))
      (node (ref "P2") (pin "2") (pinfunction "2_2") (pintype "passive"))
    )
    (net (code "62") (name "Net-(C19-Pad2)") (class "Default")
      (node (ref "C19") (pin "2") (pinfunction "2_2") (pintype "passive"))
      (node (ref "FB5") (pin "1") (pinfunction "1_1") (pintype "passive"))
      (node (ref "P2") (pin "1") (pinfunction "1_1") (pintype "passive"))
    )
    (net (code "63") (name "Net-(D4-A)") (class "Default")
      (node (ref "D4") (pin "1") (pinfunction "A_1") (pintype "passive"))
      (node (ref "D5") (pin "1") (pinfunction "A_1") (pintype "passive"))
      (node (ref "R18") (pin "2") (pinfunction "2_2") (pintype "passive"))
      (node (ref "U6") (pin "2") (pinfunction "RX_2") (pintype "bidirectional"))
    )
    (net (code "64") (name "Net-(D6-PadA)") (class "Default")
      (node (ref "D6") (pin "A") (pinfunction "A_A") (pintype "passive"))
      (node (ref "R28") (pin "1") (pinfunction "1_1") (pintype "passive"))
    )
    (net (code "65") (name "Net-(D7-PadA)") (class "Default")
      (node (ref "D7") (pin "A") (pinfunction "A_A") (pintype "passive"))
      (node (ref "R29") (pin "1") (pinfunction "1_1") (pintype "passive"))
    )
    (net (code "66") (name "Net-(D8-PadA)") (class "Default")
      (node (ref "D8") (pin "A") (pinfunction "A_A") (pintype "passive"))
      (node (ref "R30") (pin "1") (pinfunction "1_1") (pintype "passive"))
    )
    (net (code "67") (name "Net-(DC6-CATHODE)") (class "Default")
      (node (ref "DC6") (pin "2") (pinfunction "CATHODE_2") (pintype "passive"))
      (node (ref "FB4") (pin "2") (pinfunction "2_2") (pintype "passive"))
      (node (ref "U6") (pin "7") (pinfunction "PWM+_7") (pintype "output"))
    )
    (net (code "68") (name "Net-(DC7-CATHODE)") (class "Default")
      (node (ref "DC7") (pin "2") (pinfunction "CATHODE_2") (pintype "passive"))
      (node (ref "FB5") (pin "2") (pinfunction "2_2") (pintype "passive"))
      (node (ref "U6") (pin "5") (pinfunction "PWM-_5") (pintype "output"))
    )
    (net (code "69") (name "Net-(Q3-B)") (class "Default")
      (node (ref "Q3") (pin "1") (pinfunction "B_1") (pintype "passive"))
      (node (ref "R32") (pin "1") (pinfunction "1_1") (pintype "passive"))
    )
    (net (code "70") (name "Net-(Q3-C)") (class "Default")
      (node (ref "Q3") (pin "3") (pinfunction "C_3") (pintype "passive"))
      (node (ref "R31") (pin "1") (pinfunction "1_1") (pintype "passive"))
    )
    (net (code "71") (name "Net-(U7-PA9)") (class "Default")
      (node (ref "R27") (pin "2") (pinfunction "2_2") (pintype "passive"))
      (node (ref "U7") (pin "68") (pinfunction "PA9_68") (pintype "passive"))
    )
    (net (code "72") (name "Net-(U7-PA10)") (class "Default")
      (node (ref "R26") (pin "2") (pinfunction "2_2") (pintype "passive"))
      (node (ref "U7") (pin "69") (pinfunction "PA10_69") (pintype "passive"))
    )
    (net (code "73") (name "Net-(U7-PA15)") (class "Default")
      (node (ref "J9") (pin "1") (pinfunction "1_1") (pintype "passive"))
      (node (ref "U7") (pin "77") (pinfunction "PA15_77") (pintype "passive"))
    )
    (net (code "74") (name "Net-(U7-PB6)") (class "Default")
      (node (ref "J8") (pin "1") (pinfunction "1_1") (pintype "passive"))
      (node (ref "U7") (pin "92") (pinfunction "PB6_92") (pintype "passive"))
    )
    (net (code "75") (name "Net-(U7-PB7)") (class "Default")
      (node (ref "J7") (pin "1") (pinfunction "1_1") (pintype "passive"))
      (node (ref "U7") (pin "93") (pinfunction "PB7_93") (pintype "passive"))
    )
    (net (code "76") (name "Net-(U7-PB10)") (class "Default")
      (node (ref "R84") (pin "1") (pinfunction "1_1") (pintype "passive"))
      (node (ref "U7") (pin "47") (pinfunction "PB10_47") (pintype "passive"))
    )
    (net (code "77") (name "Net-(U7-PB11)") (class "Default")
      (node (ref "R83") (pin "1") (pinfunction "1_1") (pintype "passive"))
      (node (ref "U7") (pin "48") (pinfunction "PB11_48") (pintype "passive"))
    )
    (net (code "78") (name "Net-(U7-PC7)") (class "Default")
      (node (ref "R28") (pin "2") (pinfunction "2_2") (pintype "passive"))
      (node (ref "U7") (pin "64") (pinfunction "PC7_64") (pintype "passive"))
    )
    (net (code "79") (name "Net-(U7-PC8)") (class "Default")
      (node (ref "R29") (pin "2") (pinfunction "2_2") (pintype "passive"))
      (node (ref "U7") (pin "65") (pinfunction "PC8_65") (pintype "passive"))
    )
    (net (code "80") (name "Net-(U7-PC9)") (class "Default")
      (node (ref "R30") (pin "2") (pinfunction "2_2") (pintype "passive"))
      (node (ref "U7") (pin "66") (pinfunction "PC9_66") (pintype "passive"))
    )
    (net (code "81") (name "Net-(U7-PC10)") (class "Default")
      (node (ref "R24") (pin "2") (pinfunction "2_2") (pintype "passive"))
      (node (ref "U7") (pin "78") (pinfunction "PC10_78") (pintype "passive"))
    )
    (net (code "82") (name "Net-(U7-PC11)") (class "Default")
      (node (ref "R25") (pin "2") (pinfunction "2_2") (pintype "passive"))
      (node (ref "U7") (pin "79") (pinfunction "PC11_79") (pintype "passive"))
    )
    (net (code "83") (name "SPK_3V3") (class "Default")
      (node (ref "C13") (pin "1") (pinfunction "1_1") (pintype "passive"))
      (node (ref "C14") (pin "2") (pinfunction "2_2") (pintype "passive"))
      (node (ref "U6") (pin "6") (pinfunction "VCC_6") (pintype "power_in"))
    )
    (net (code "84") (name "VCC_3.3V") (class "Default")
      (node (ref "C25") (pin "2") (pinfunction "2_2") (pintype "passive"))
      (node (ref "C26") (pin "2") (pinfunction "2_2") (pintype "passive"))
      (node (ref "C27") (pin "2") (pinfunction "2_2") (pintype "passive"))
      (node (ref "C28") (pin "2") (pinfunction "2_2") (pintype "passive"))
      (node (ref "J5") (pin "33") (pinfunction "A_33") (pintype "passive"))
      (node (ref "P3") (pin "1") (pinfunction "1_1") (pintype "passive"))
      (node (ref "P4") (pin "1") (pinfunction "1_1") (pintype "passive"))
      (node (ref "P5") (pin "1") (pinfunction "1_1") (pintype "passive"))
      (node (ref "R16") (pin "2") (pinfunction "2_2") (pintype "passive"))
      (node (ref "R17") (pin "2") (pinfunction "2_2") (pintype "passive"))
      (node (ref "R18") (pin "1") (pinfunction "1_1") (pintype "passive"))
      (node (ref "R19") (pin "2") (pinfunction "2_2") (pintype "passive"))
      (node (ref "R20") (pin "2") (pinfunction "2_2") (pintype "passive"))
      (node (ref "R21") (pin "2") (pinfunction "2_2") (pintype "passive"))
      (node (ref "R22") (pin "2") (pinfunction "2_2") (pintype "passive"))
      (node (ref "U7") (pin "100") (pinfunction "VDD_100") (pintype "passive"))
      (node (ref "U7") (pin "11") (pinfunction "VDD_11") (pintype "passive"))
      (node (ref "U7") (pin "28") (pinfunction "VDD_28") (pintype "passive"))
      (node (ref "U7") (pin "50") (pinfunction "VDD_50") (pintype "passive"))
      (node (ref "U7") (pin "75") (pinfunction "VDD_75") (pintype "passive"))
    )
    (net (code "85") (name "VDDA") (class "Default")
      (node (ref "U7") (pin "21") (pinfunction "VREF+_21") (pintype "passive"))
      (node (ref "U7") (pin "22") (pinfunction "VDDA_22") (pintype "passive"))
    )
    (net (code "86") (name "unconnected-(J5-SDO-Pad14)") (class "Default")
      (node (ref "J5") (pin "14") (pinfunction "SDO_14") (pintype "passive"))
    )
    (net (code "87") (name "unconnected-(J5-TE-Pad8)") (class "Default")
      (node (ref "J5") (pin "8") (pinfunction "TE_8") (pintype "passive"))
    )
    (net (code "88") (name "unconnected-(J5-XL(NC)-Pad1)") (class "Default")
      (node (ref "J5") (pin "1") (pinfunction "XL(NC)_1") (pintype "passive"))
    )
    (net (code "89") (name "unconnected-(J5-XR(NC)-Pad3)") (class "Default")
      (node (ref "J5") (pin "3") (pinfunction "XR(NC)_3") (pintype "passive"))
    )
    (net (code "90") (name "unconnected-(J5-YD(NC)-Pad4)") (class "Default")
      (node (ref "J5") (pin "4") (pinfunction "YD(NC)_4") (pintype "passive"))
    )
    (net (code "91") (name "unconnected-(J5-YU(NC)-Pad2)") (class "Default")
      (node (ref "J5") (pin "2") (pinfunction "YU(NC)_2") (pintype "passive"))
    )
    (net (code "92") (name "unconnected-(U6-IN+-Pad3)") (class "Default")
      (node (ref "U6") (pin "3") (pinfunction "IN+_3") (pintype "input"))
    )
    (net (code "93") (name "unconnected-(U6-IN--Pad4)") (class "Default")
      (node (ref "U6") (pin "4") (pinfunction "IN-_4") (pintype "power_in"))
    )
    (net (code "94") (name "unconnected-(U7-NC-Pad73)") (class "Default")
      (node (ref "U7") (pin "73") (pinfunction "NC_73") (pintype "passive"))
    )
    (net (code "95") (name "unconnected-(U7-PA6-Pad31)") (class "Default")
      (node (ref "U7") (pin "31") (pinfunction "PA6_31") (pintype "passive"))
    )
    (net (code "96") (name "unconnected-(U7-PA7-Pad32)") (class "Default")
      (node (ref "U7") (pin "32") (pinfunction "PA7_32") (pintype "passive"))
    )
    (net (code "97") (name "unconnected-(U7-PA8-Pad67)") (class "Default")
      (node (ref "U7") (pin "67") (pinfunction "PA8_67") (pintype "passive"))
    )
    (net (code "98") (name "unconnected-(U7-PB4-Pad90)") (class "Default")
      (node (ref "U7") (pin "90") (pinfunction "PB4_90") (pintype "passive"))
    )
    (net (code "99") (name "unconnected-(U7-PB5-Pad91)") (class "Default")
      (node (ref "U7") (pin "91") (pinfunction "PB5_91") (pintype "passive"))
    )
    (net (code "100") (name "unconnected-(U7-PC0-Pad15)") (class "Default")
      (node (ref "U7") (pin "15") (pinfunction "PC0_15") (pintype "passive"))
    )
    (net (code "101") (name "unconnected-(U7-PC1-Pad16)") (class "Default")
      (node (ref "U7") (pin "16") (pinfunction "PC1_16") (pintype "passive"))
    )
    (net (code "102") (name "unconnected-(U7-PC2-Pad17)") (class "Default")
      (node (ref "U7") (pin "17") (pinfunction "PC2_17") (pintype "passive"))
    )
    (net (code "103") (name "unconnected-(U7-PC3-Pad18)") (class "Default")
      (node (ref "U7") (pin "18") (pinfunction "PC3_18") (pintype "passive"))
    )
    (net (code "104") (name "unconnected-(U7-PC4-Pad33)") (class "Default")
      (node (ref "U7") (pin "33") (pinfunction "PC4_33") (pintype "passive"))
    )
    (net (code "105") (name "unconnected-(U7-PC6-Pad63)") (class "Default")
      (node (ref "U7") (pin "63") (pinfunction "PC6_63") (pintype "passive"))
    )
    (net (code "106") (name "unconnected-(U7-PC12-Pad80)") (class "Default")
      (node (ref "U7") (pin "80") (pinfunction "PC12_80") (pintype "passive"))
    )
    (net (code "107") (name "unconnected-(U7-PC13-Pad7)") (class "Default")
      (node (ref "U7") (pin "7") (pinfunction "PC13_7") (pintype "passive"))
    )
    (net (code "108") (name "unconnected-(U7-PC14-OSC32_IN-Pad8)") (class "Default")
      (node (ref "U7") (pin "8") (pinfunction "PC14-OSC32_IN_8") (pintype "passive"))
    )
    (net (code "109") (name "unconnected-(U7-PC15-OSC32_OUT-Pad9)") (class "Default")
      (node (ref "U7") (pin "9") (pinfunction "PC15-OSC32_OUT_9") (pintype "passive"))
    )
    (net (code "110") (name "unconnected-(U7-PE1-Pad98)") (class "Default")
      (node (ref "U7") (pin "98") (pinfunction "PE1_98") (pintype "passive"))
    )
    (net (code "111") (name "unconnected-(U7-PE8-Pad39)") (class "Default")
      (node (ref "U7") (pin "39") (pinfunction "PE8_39") (pintype "passive"))
    )
    (net (code "112") (name "unconnected-(U7-PE9-Pad40)") (class "Default")
      (node (ref "U7") (pin "40") (pinfunction "PE9_40") (pintype "passive"))
    )
    (net (code "113") (name "unconnected-(U7-PE12-Pad43)") (class "Default")
      (node (ref "U7") (pin "43") (pinfunction "PE12_43") (pintype "passive"))
    )
    (net (code "114") (name "unconnected-(U7-PE13-Pad44)") (class "Default")
      (node (ref "U7") (pin "44") (pinfunction "PE13_44") (pintype "passive"))
    )
    (net (code "115") (name "unconnected-(U7-PE14-Pad45)") (class "Default")
      (node (ref "U7") (pin "45") (pinfunction "PE14_45") (pintype "passive"))
    )
    (net (code "116") (name "unconnected-(U7-PE15-Pad46)") (class "Default")
      (node (ref "U7") (pin "46") (pinfunction "PE15_46") (pintype "passive"))
    )
    (net (code "117") (name "unconnected-(U7-VBAT-Pad6)") (class "Default")
      (node (ref "U7") (pin "6") (pinfunction "VBAT_6") (pintype "passive"))
    )
  )
)
